# BI1.net
KiCad netlist of a schematic drawn in Altium Designer
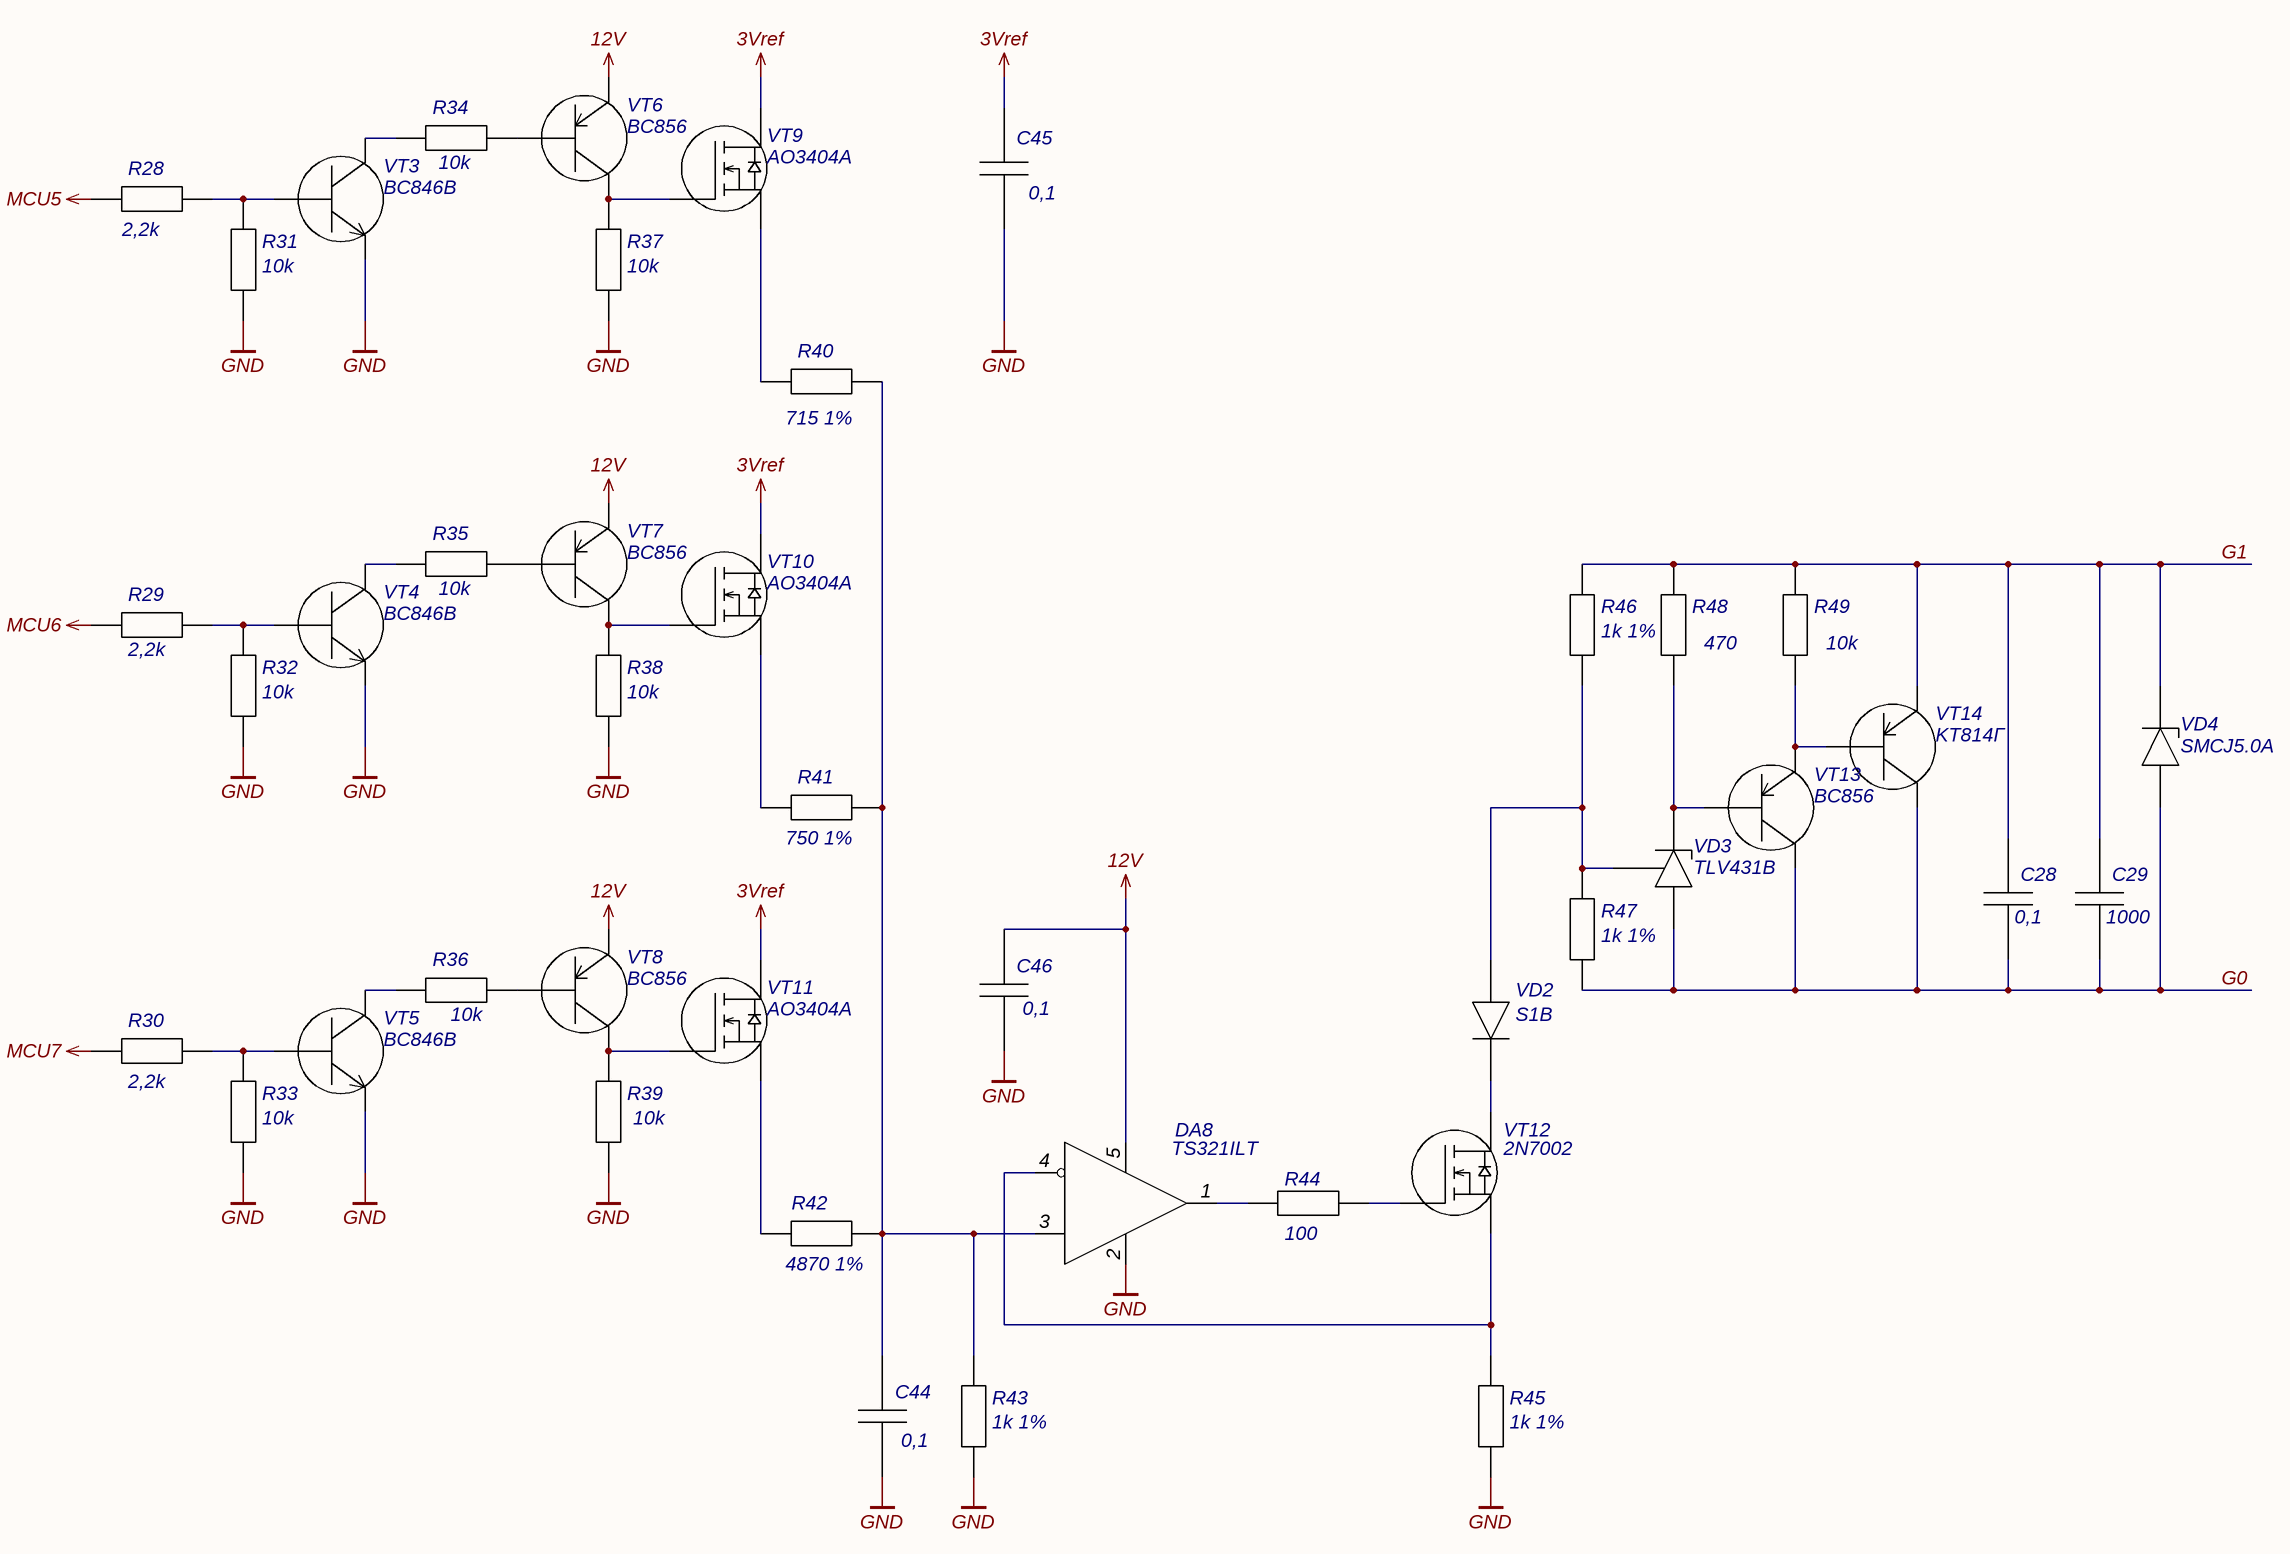
[diagram p0: BI1.SchDoc]

(export (version "E")
  (design (tool "Eeschema 10.0.6"))
  (components
    (comp (ref "C28")
      (value "0,1")
      (footprint "C0603")
      (description "Чип-конденсатор")
      (libsource (lib "Passive") (part "Chip Capasitor"))
    )
    (comp (ref "C29")
      (value "1000")
      (footprint "C0603")
      (description "Чип-конденсатор")
      (libsource (lib "Passive") (part "Chip Capasitor"))
    )
    (comp (ref "C44")
      (value "0,1")
      (footprint "C0603")
      (description "Чип-конденсатор")
      (libsource (lib "Passive") (part "Chip Capasitor"))
    )
    (comp (ref "C45")
      (value "0,1")
      (footprint "C0603")
      (description "Чип-конденсатор")
      (libsource (lib "Passive") (part "Chip Capasitor"))
    )
    (comp (ref "C46")
      (value "0,1")
      (footprint "C0603")
      (description "Чип-конденсатор")
      (libsource (lib "Passive") (part "Chip Capasitor"))
    )
    (comp (ref "DA8")
      (value "TS321ILT")
      (footprint "SOT-23-5")
      (description "1х Операционный усилитель")
      (libsource (lib "Schlib") (part "TS321ILT"))
    )
    (comp (ref "R28")
      (value "2,2k")
      (footprint "R0603")
      (description "Чип-резистор")
      (libsource (lib "") (part "Chip Resistor_1"))
    )
    (comp (ref "R29")
      (value "2,2k")
      (footprint "R0603")
      (description "Чип-резистор")
      (libsource (lib "") (part "Chip Resistor_1"))
    )
    (comp (ref "R30")
      (value "2,2k")
      (footprint "R0603")
      (description "Чип-резистор")
      (libsource (lib "") (part "Chip Resistor_1"))
    )
    (comp (ref "R31")
      (value "10k")
      (footprint "R0603")
      (description "Чип-резистор")
      (libsource (lib "Passive") (part "Chip Resistor"))
    )
    (comp (ref "R32")
      (value "10k")
      (footprint "R0603")
      (description "Чип-резистор")
      (libsource (lib "Passive") (part "Chip Resistor"))
    )
    (comp (ref "R33")
      (value "10k")
      (footprint "R0603")
      (description "Чип-резистор")
      (libsource (lib "Passive") (part "Chip Resistor"))
    )
    (comp (ref "R34")
      (value "10k")
      (footprint "R0603")
      (description "Чип-резистор")
      (libsource (lib "") (part "Chip Resistor_1"))
    )
    (comp (ref "R35")
      (value "10k")
      (footprint "R0603")
      (description "Чип-резистор")
      (libsource (lib "") (part "Chip Resistor_1"))
    )
    (comp (ref "R36")
      (value "10k")
      (footprint "R0603")
      (description "Чип-резистор")
      (libsource (lib "") (part "Chip Resistor_1"))
    )
    (comp (ref "R37")
      (value "10k")
      (footprint "R0603")
      (description "Чип-резистор")
      (libsource (lib "Passive") (part "Chip Resistor"))
    )
    (comp (ref "R38")
      (value "10k")
      (footprint "R0603")
      (description "Чип-резистор")
      (libsource (lib "Passive") (part "Chip Resistor"))
    )
    (comp (ref "R39")
      (value "10k")
      (footprint "R0603")
      (description "Чип-резистор")
      (libsource (lib "Passive") (part "Chip Resistor"))
    )
    (comp (ref "R40")
      (value "715 1%")
      (footprint "R0603")
      (description "Чип-резистор")
      (fields (field (name "PARTNUMBER") "RC0603FR-07715RL"))
      (libsource (lib "") (part "Chip Resistor_1"))
    )
    (comp (ref "R41")
      (value "750 1%")
      (footprint "R0603")
      (description "Чип-резистор")
      (fields (field (name "PARTNUMBER") "RC0603FR-07750RL"))
      (libsource (lib "") (part "Chip Resistor_1"))
    )
    (comp (ref "R42")
      (value "4870 1%")
      (footprint "R0603")
      (description "Чип-резистор")
      (fields (field (name "PARTNUMBER") "RC0603FR-074K87L"))
      (libsource (lib "") (part "Chip Resistor_1"))
    )
    (comp (ref "R43")
      (value "1k 1%")
      (footprint "R0603")
      (description "Чип-резистор")
      (fields (field (name "PARTNUMBER") "CRCW06031K00FKEAC"))
      (libsource (lib "Passive") (part "Chip Resistor"))
    )
    (comp (ref "R44")
      (value "100")
      (footprint "R0603")
      (description "Чип-резистор")
      (libsource (lib "") (part "Chip Resistor_1"))
    )
    (comp (ref "R45")
      (value "1k 1%")
      (footprint "R0603")
      (description "Чип-резистор")
      (fields (field (name "PARTNUMBER") "CRCW06031K00FKEAC"))
      (libsource (lib "Passive") (part "Chip Resistor"))
    )
    (comp (ref "R46")
      (value "1k 1%")
      (footprint "R0603")
      (description "Чип-резистор")
      (fields (field (name "PARTNUMBER") "CRCW06031K00FKEAC"))
      (libsource (lib "Passive") (part "Chip Resistor"))
    )
    (comp (ref "R47")
      (value "1k 1%")
      (footprint "R0603")
      (description "Чип-резистор")
      (fields (field (name "PARTNUMBER") "CRCW06031K00FKEAC"))
      (libsource (lib "Passive") (part "Chip Resistor"))
    )
    (comp (ref "R48")
      (value "470")
      (footprint "R0603")
      (description "Чип-резистор")
      (libsource (lib "Passive") (part "Chip Resistor"))
    )
    (comp (ref "R49")
      (value "10k")
      (footprint "R0603")
      (description "Чип-резистор")
      (libsource (lib "Passive") (part "Chip Resistor"))
    )
    (comp (ref "VD2")
      (value "S1B")
      (footprint "DO-214AC")
      (description "Диод выпрямительный, 100В")
      (fields (field (name "MANUFACTURER") "Diotec Semiconductor"))
      (libsource (lib "Schlib") (part "S1B"))
    )
    (comp (ref "VD3")
      (value "TLV431B")
      (footprint "SOT-23")
      (description "Стабилитрон регулируемый, 6В")
      (fields (field (name "MANUFACTURER") "Texas Instruments"))
      (libsource (lib "Schlib") (part "TLV431B"))
    )
    (comp (ref "VD4")
      (value "SMCJ5.0A")
      (footprint "DO-214AB")
      (description "Защитный диод, 5В")
      (fields (field (name "MANUFACTURER") "UTD Semiconductor Co.,Ltd"))
      (libsource (lib "Schlib") (part "SMCJ5.0A"))
    )
    (comp (ref "VT3")
      (value "BC846B")
      (footprint "SOT-23")
      (description "Транзистор биполярный NPN, 65В")
      (fields (field (name "MANUFACTURER") "Nexperia B.V."))
      (libsource (lib "Schlib") (part "BC846B"))
    )
    (comp (ref "VT4")
      (value "BC846B")
      (footprint "SOT-23")
      (description "Транзистор биполярный NPN, 65В")
      (fields (field (name "MANUFACTURER") "Nexperia B.V."))
      (libsource (lib "Schlib") (part "BC846B"))
    )
    (comp (ref "VT5")
      (value "BC846B")
      (footprint "SOT-23")
      (description "Транзистор биполярный NPN, 65В")
      (fields (field (name "MANUFACTURER") "Nexperia B.V."))
      (libsource (lib "Schlib") (part "BC846B"))
    )
    (comp (ref "VT6")
      (value "BC856")
      (footprint "SOT-23")
      (description "Транзистор биполярный PNP, 65В")
      (fields (field (name "MANUFACTURER") "Nexperia"))
      (libsource (lib "Schlib") (part "BC856"))
    )
    (comp (ref "VT7")
      (value "BC856")
      (footprint "SOT-23")
      (description "Транзистор биполярный PNP, 65В")
      (fields (field (name "MANUFACTURER") "Nexperia"))
      (libsource (lib "Schlib") (part "BC856"))
    )
    (comp (ref "VT8")
      (value "BC856")
      (footprint "SOT-23")
      (description "Транзистор биполярный PNP, 65В")
      (fields (field (name "MANUFACTURER") "Nexperia"))
      (libsource (lib "Schlib") (part "BC856"))
    )
    (comp (ref "VT9")
      (value "AO3404A")
      (footprint "SOT-23")
      (description "Транзистор MOSFET N-канал, 30В")
      (fields (field (name "MANUFACTURER") "UTD Semiconductor Co.,Ltd"))
      (libsource (lib "Schlib") (part "AO3404A"))
    )
    (comp (ref "VT10")
      (value "AO3404A")
      (footprint "SOT-23")
      (description "Транзистор MOSFET N-канал, 30В")
      (fields (field (name "MANUFACTURER") "UTD Semiconductor Co.,Ltd"))
      (libsource (lib "Schlib") (part "AO3404A"))
    )
    (comp (ref "VT11")
      (value "AO3404A")
      (footprint "SOT-23")
      (description "Транзистор MOSFET N-канал, 30В")
      (fields (field (name "MANUFACTURER") "UTD Semiconductor Co.,Ltd"))
      (libsource (lib "Schlib") (part "AO3404A"))
    )
    (comp (ref "VT12")
      (value "2N7002")
      (footprint "SOT-23")
      (description "Транзистор MOSFET N-канал, 60В")
      (fields (field (name "MANUFACTURER") "UTD Semiconductor Co."))
      (libsource (lib "Schlib") (part "2N7002"))
    )
    (comp (ref "VT13")
      (value "BC856")
      (footprint "SOT-23")
      (description "Транзистор биполярный PNP, 65В")
      (fields (field (name "MANUFACTURER") "Nexperia"))
      (libsource (lib "Schlib") (part "BC856"))
    )
    (comp (ref "VT14")
      (value "KT814Г")
      (footprint "TO-126")
      (description "Транзистор биполярный PNP, 100В")
      (fields (field (name "MANUFACTURER") "АО «ГРУППА КРЕМНИЙ ЭЛ»"))
      (libsource (lib "Schlib") (part "KT814Г"))
    )
  )
  (nets
    (net (code "1") (name "/G0") (class "Default")
      (node (ref "C28") (pin "1") (pinfunction "1_1") (pintype "passive"))
      (node (ref "C29") (pin "1") (pinfunction "1_1") (pintype "passive"))
      (node (ref "R47") (pin "1") (pinfunction "1_1") (pintype "passive"))
      (node (ref "VD3") (pin "1") (pinfunction "1_1") (pintype "passive"))
      (node (ref "VD4") (pin "1") (pinfunction "1_1") (pintype "passive"))
      (node (ref "VT13") (pin "2") (pinfunction "2_2") (pintype "passive"))
      (node (ref "VT14") (pin "2") (pinfunction "2_2") (pintype "passive"))
    )
    (net (code "2") (name "/G1") (class "Default")
      (node (ref "C28") (pin "2") (pinfunction "2_2") (pintype "passive"))
      (node (ref "C29") (pin "2") (pinfunction "2_2") (pintype "passive"))
      (node (ref "R46") (pin "2") (pinfunction "2_2") (pintype "passive"))
      (node (ref "R48") (pin "2") (pinfunction "2_2") (pintype "passive"))
      (node (ref "R49") (pin "2") (pinfunction "2_2") (pintype "passive"))
      (node (ref "VD4") (pin "2") (pinfunction "2_2") (pintype "passive"))
      (node (ref "VT14") (pin "1") (pinfunction "1_1") (pintype "passive"))
    )
    (net (code "3") (name "3Vref") (class "Default")
      (node (ref "C45") (pin "2") (pinfunction "2_2") (pintype "passive"))
      (node (ref "VT10") (pin "2") (pinfunction "D_2") (pintype "passive"))
      (node (ref "VT11") (pin "2") (pinfunction "D_2") (pintype "passive"))
      (node (ref "VT9") (pin "2") (pinfunction "D_2") (pintype "passive"))
    )
    (net (code "4") (name "12V") (class "Default")
      (node (ref "C46") (pin "2") (pinfunction "2_2") (pintype "passive"))
      (node (ref "DA8") (pin "5") (pinfunction "Vcc_5") (pintype "passive"))
      (node (ref "VT6") (pin "1") (pinfunction "1_1") (pintype "passive"))
      (node (ref "VT7") (pin "1") (pinfunction "1_1") (pintype "passive"))
      (node (ref "VT8") (pin "1") (pinfunction "1_1") (pintype "passive"))
    )
    (net (code "5") (name "GND") (class "Default")
      (node (ref "C44") (pin "1") (pinfunction "1_1") (pintype "passive"))
      (node (ref "C45") (pin "1") (pinfunction "1_1") (pintype "passive"))
      (node (ref "C46") (pin "1") (pinfunction "1_1") (pintype "passive"))
      (node (ref "DA8") (pin "2") (pinfunction "GND_2") (pintype "passive"))
      (node (ref "R31") (pin "1") (pinfunction "1_1") (pintype "passive"))
      (node (ref "R32") (pin "1") (pinfunction "1_1") (pintype "passive"))
      (node (ref "R33") (pin "1") (pinfunction "1_1") (pintype "passive"))
      (node (ref "R37") (pin "1") (pinfunction "1_1") (pintype "passive"))
      (node (ref "R38") (pin "1") (pinfunction "1_1") (pintype "passive"))
      (node (ref "R39") (pin "1") (pinfunction "1_1") (pintype "passive"))
      (node (ref "R43") (pin "1") (pinfunction "1_1") (pintype "passive"))
      (node (ref "R45") (pin "1") (pinfunction "1_1") (pintype "passive"))
      (node (ref "VT3") (pin "2") (pinfunction "E_2") (pintype "passive"))
      (node (ref "VT4") (pin "2") (pinfunction "E_2") (pintype "passive"))
      (node (ref "VT5") (pin "2") (pinfunction "E_2") (pintype "passive"))
    )
    (net (code "6") (name "MCU5") (class "Default")
      (node (ref "R28") (pin "1") (pinfunction "1_1") (pintype "passive"))
    )
    (net (code "7") (name "MCU6") (class "Default")
      (node (ref "R29") (pin "1") (pinfunction "1_1") (pintype "passive"))
    )
    (net (code "8") (name "MCU7") (class "Default")
      (node (ref "R30") (pin "1") (pinfunction "1_1") (pintype "passive"))
    )
    (net (code "9") (name "Net-(DA8-+)") (class "Default")
      (node (ref "C44") (pin "2") (pinfunction "2_2") (pintype "passive"))
      (node (ref "DA8") (pin "3") (pinfunction "+_3") (pintype "passive"))
      (node (ref "R40") (pin "2") (pinfunction "2_2") (pintype "passive"))
      (node (ref "R41") (pin "2") (pinfunction "2_2") (pintype "passive"))
      (node (ref "R42") (pin "2") (pinfunction "2_2") (pintype "passive"))
      (node (ref "R43") (pin "2") (pinfunction "2_2") (pintype "passive"))
    )
    (net (code "10") (name "Net-(DA8--)") (class "Default")
      (node (ref "DA8") (pin "4") (pinfunction "-_4") (pintype "passive"))
      (node (ref "R45") (pin "2") (pinfunction "2_2") (pintype "passive"))
      (node (ref "VT12") (pin "3") (pinfunction "S_3") (pintype "passive"))
    )
    (net (code "11") (name "Net-(DA8-OUT)") (class "Default")
      (node (ref "DA8") (pin "1") (pinfunction "OUT_1") (pintype "passive"))
      (node (ref "R44") (pin "1") (pinfunction "1_1") (pintype "passive"))
    )
    (net (code "12") (name "Net-(R34-Pad2)") (class "Default")
      (node (ref "R34") (pin "2") (pinfunction "2_2") (pintype "passive"))
      (node (ref "VT6") (pin "3") (pinfunction "3_3") (pintype "passive"))
    )
    (net (code "13") (name "Net-(R35-Pad2)") (class "Default")
      (node (ref "R35") (pin "2") (pinfunction "2_2") (pintype "passive"))
      (node (ref "VT7") (pin "3") (pinfunction "3_3") (pintype "passive"))
    )
    (net (code "14") (name "Net-(R36-Pad2)") (class "Default")
      (node (ref "R36") (pin "2") (pinfunction "2_2") (pintype "passive"))
      (node (ref "VT8") (pin "3") (pinfunction "3_3") (pintype "passive"))
    )
    (net (code "15") (name "Net-(R46-Pad1)") (class "Default")
      (node (ref "R46") (pin "1") (pinfunction "1_1") (pintype "passive"))
      (node (ref "R47") (pin "2") (pinfunction "2_2") (pintype "passive"))
      (node (ref "VD2") (pin "1") (pinfunction "1_1") (pintype "passive"))
      (node (ref "VD3") (pin "3") (pinfunction "3_3") (pintype "passive"))
    )
    (net (code "16") (name "Net-(R48-Pad1)") (class "Default")
      (node (ref "R48") (pin "1") (pinfunction "1_1") (pintype "passive"))
      (node (ref "VD3") (pin "2") (pinfunction "2_2") (pintype "passive"))
      (node (ref "VT13") (pin "3") (pinfunction "3_3") (pintype "passive"))
    )
    (net (code "17") (name "Net-(R49-Pad1)") (class "Default")
      (node (ref "R49") (pin "1") (pinfunction "1_1") (pintype "passive"))
      (node (ref "VT13") (pin "1") (pinfunction "1_1") (pintype "passive"))
      (node (ref "VT14") (pin "3") (pinfunction "3_3") (pintype "passive"))
    )
    (net (code "18") (name "Net-(VT3-B)") (class "Default")
      (node (ref "R28") (pin "2") (pinfunction "2_2") (pintype "passive"))
      (node (ref "R31") (pin "2") (pinfunction "2_2") (pintype "passive"))
      (node (ref "VT3") (pin "1") (pinfunction "B_1") (pintype "passive"))
    )
    (net (code "19") (name "Net-(VT3-C)") (class "Default")
      (node (ref "R34") (pin "1") (pinfunction "1_1") (pintype "passive"))
      (node (ref "VT3") (pin "3") (pinfunction "C_3") (pintype "passive"))
    )
    (net (code "20") (name "Net-(VT4-B)") (class "Default")
      (node (ref "R29") (pin "2") (pinfunction "2_2") (pintype "passive"))
      (node (ref "R32") (pin "2") (pinfunction "2_2") (pintype "passive"))
      (node (ref "VT4") (pin "1") (pinfunction "B_1") (pintype "passive"))
    )
    (net (code "21") (name "Net-(VT4-C)") (class "Default")
      (node (ref "R35") (pin "1") (pinfunction "1_1") (pintype "passive"))
      (node (ref "VT4") (pin "3") (pinfunction "C_3") (pintype "passive"))
    )
    (net (code "22") (name "Net-(VT5-B)") (class "Default")
      (node (ref "R30") (pin "2") (pinfunction "2_2") (pintype "passive"))
      (node (ref "R33") (pin "2") (pinfunction "2_2") (pintype "passive"))
      (node (ref "VT5") (pin "1") (pinfunction "B_1") (pintype "passive"))
    )
    (net (code "23") (name "Net-(VT5-C)") (class "Default")
      (node (ref "R36") (pin "1") (pinfunction "1_1") (pintype "passive"))
      (node (ref "VT5") (pin "3") (pinfunction "C_3") (pintype "passive"))
    )
    (net (code "24") (name "Net-(VT9-G)") (class "Default")
      (node (ref "R37") (pin "2") (pinfunction "2_2") (pintype "passive"))
      (node (ref "VT6") (pin "2") (pinfunction "2_2") (pintype "passive"))
      (node (ref "VT9") (pin "1") (pinfunction "G_1") (pintype "passive"))
    )
    (net (code "25") (name "Net-(VT9-S)") (class "Default")
      (node (ref "R40") (pin "1") (pinfunction "1_1") (pintype "passive"))
      (node (ref "VT9") (pin "3") (pinfunction "S_3") (pintype "passive"))
    )
    (net (code "26") (name "Net-(VT10-G)") (class "Default")
      (node (ref "R38") (pin "2") (pinfunction "2_2") (pintype "passive"))
      (node (ref "VT10") (pin "1") (pinfunction "G_1") (pintype "passive"))
      (node (ref "VT7") (pin "2") (pinfunction "2_2") (pintype "passive"))
    )
    (net (code "27") (name "Net-(VT10-S)") (class "Default")
      (node (ref "R41") (pin "1") (pinfunction "1_1") (pintype "passive"))
      (node (ref "VT10") (pin "3") (pinfunction "S_3") (pintype "passive"))
    )
    (net (code "28") (name "Net-(VT11-G)") (class "Default")
      (node (ref "R39") (pin "2") (pinfunction "2_2") (pintype "passive"))
      (node (ref "VT11") (pin "1") (pinfunction "G_1") (pintype "passive"))
      (node (ref "VT8") (pin "2") (pinfunction "2_2") (pintype "passive"))
    )
    (net (code "29") (name "Net-(VT11-S)") (class "Default")
      (node (ref "R42") (pin "1") (pinfunction "1_1") (pintype "passive"))
      (node (ref "VT11") (pin "3") (pinfunction "S_3") (pintype "passive"))
    )
    (net (code "30") (name "Net-(VT12-D)") (class "Default")
      (node (ref "VD2") (pin "2") (pinfunction "2_2") (pintype "passive"))
      (node (ref "VT12") (pin "2") (pinfunction "D_2") (pintype "passive"))
    )
    (net (code "31") (name "Net-(VT12-G)") (class "Default")
      (node (ref "R44") (pin "2") (pinfunction "2_2") (pintype "passive"))
      (node (ref "VT12") (pin "1") (pinfunction "G_1") (pintype "passive"))
    )
  )
)
